# Scan.net
KiCad netlist of a schematic drawn in Altium Designer
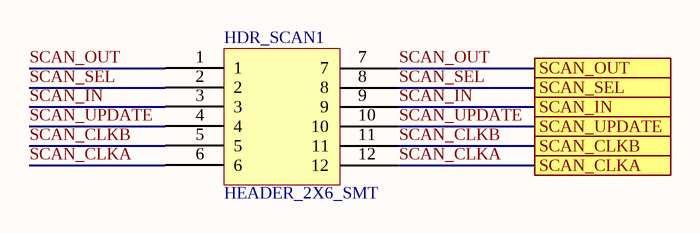
[diagram p0: Scan.SchDoc]

(export (version "E")
  (design (tool "Eeschema 10.0.6"))
  (components
    (comp (ref "HDR_SCAN1")
      (value "HEADER_2X6_SMT")
      (footprint "HDR2X6_SMT")
      (libsource (lib "200G_TX_LIB") (part "HEADER_2X6_SMT"))
    )
  )
  (nets
    (net (code "1") (name "/SCAN_CLKA") (class "Default")
      (node (ref "HDR_SCAN1") (pin "12") (pinfunction "12_12") (pintype "passive"))
      (node (ref "HDR_SCAN1") (pin "6") (pinfunction "6_6") (pintype "passive"))
    )
    (net (code "2") (name "/SCAN_CLKB") (class "Default")
      (node (ref "HDR_SCAN1") (pin "11") (pinfunction "11_11") (pintype "passive"))
      (node (ref "HDR_SCAN1") (pin "5") (pinfunction "5_5") (pintype "passive"))
    )
    (net (code "3") (name "/SCAN_IN") (class "Default")
      (node (ref "HDR_SCAN1") (pin "3") (pinfunction "3_3") (pintype "passive"))
      (node (ref "HDR_SCAN1") (pin "9") (pinfunction "9_9") (pintype "passive"))
    )
    (net (code "4") (name "/SCAN_OUT") (class "Default")
      (node (ref "HDR_SCAN1") (pin "1") (pinfunction "1_1") (pintype "passive"))
      (node (ref "HDR_SCAN1") (pin "7") (pinfunction "7_7") (pintype "passive"))
    )
    (net (code "5") (name "/SCAN_SEL") (class "Default")
      (node (ref "HDR_SCAN1") (pin "2") (pinfunction "2_2") (pintype "passive"))
      (node (ref "HDR_SCAN1") (pin "8") (pinfunction "8_8") (pintype "passive"))
    )
    (net (code "6") (name "/SCAN_UPDATE") (class "Default")
      (node (ref "HDR_SCAN1") (pin "10") (pinfunction "10_10") (pintype "passive"))
      (node (ref "HDR_SCAN1") (pin "4") (pinfunction "4_4") (pintype "passive"))
    )
  )
)
